# encoder.net
KiCad netlist of a schematic drawn in Altium Designer
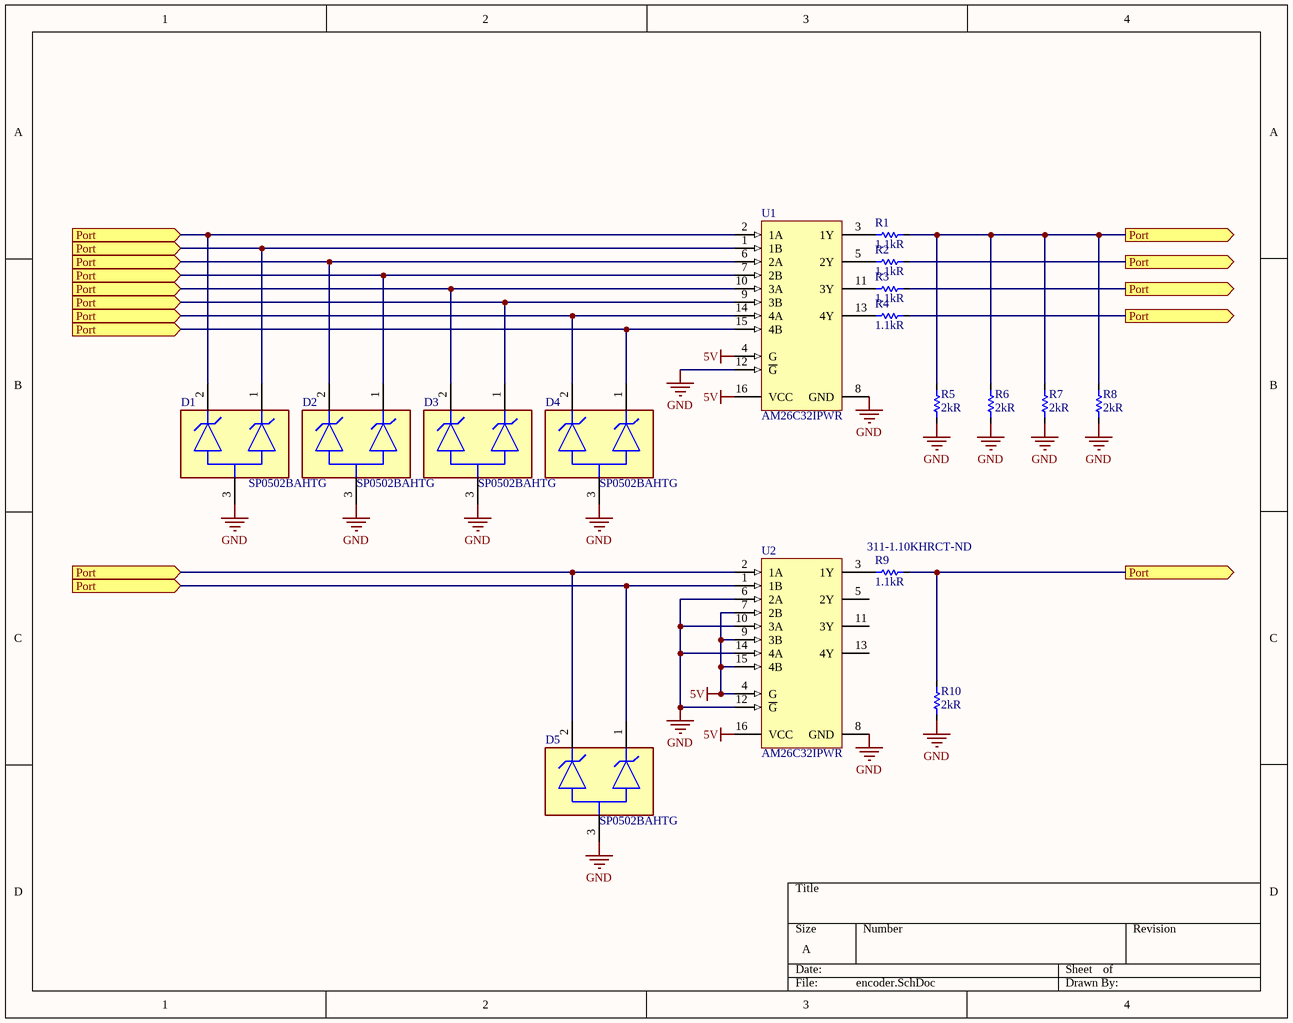
[diagram p0: encoder.SchDoc]

(export (version "E")
  (design (tool "Eeschema 10.0.6"))
  (components
    (comp (ref "D1")
      (value "SP0502BAHTG")
      (footprint "FP-SP0502BAH-MFG")
      (description "8.5V Clamp Ipp Tvs Diode Surface Mount SOT-23-3")
      (fields (field (name "OCTOPART") "https://octopart.com/sp0502bahtg-littelfuse-66370"))
      (libsource (lib "Altium Content Vault") (part "029d71e643ebb86ed7cc400ee026b5c"))
    )
    (comp (ref "D2")
      (value "SP0502BAHTG")
      (footprint "FP-SP0502BAH-MFG")
      (description "8.5V Clamp Ipp Tvs Diode Surface Mount SOT-23-3")
      (fields (field (name "OCTOPART") "https://octopart.com/sp0502bahtg-littelfuse-66370"))
      (libsource (lib "Altium Content Vault") (part "029d71e643ebb86ed7cc400ee026b5c"))
    )
    (comp (ref "D3")
      (value "SP0502BAHTG")
      (footprint "FP-SP0502BAH-MFG")
      (description "8.5V Clamp Ipp Tvs Diode Surface Mount SOT-23-3")
      (fields (field (name "OCTOPART") "https://octopart.com/sp0502bahtg-littelfuse-66370"))
      (libsource (lib "Altium Content Vault") (part "029d71e643ebb86ed7cc400ee026b5c"))
    )
    (comp (ref "D4")
      (value "SP0502BAHTG")
      (footprint "FP-SP0502BAH-MFG")
      (description "8.5V Clamp Ipp Tvs Diode Surface Mount SOT-23-3")
      (fields (field (name "OCTOPART") "https://octopart.com/sp0502bahtg-littelfuse-66370"))
      (libsource (lib "Altium Content Vault") (part "029d71e643ebb86ed7cc400ee026b5c"))
    )
    (comp (ref "D5")
      (value "SP0502BAHTG")
      (footprint "FP-SP0502BAH-MFG")
      (description "8.5V Clamp Ipp Tvs Diode Surface Mount SOT-23-3")
      (fields (field (name "OCTOPART") "https://octopart.com/sp0502bahtg-littelfuse-66370"))
      (libsource (lib "Altium Content Vault") (part "029d71e643ebb86ed7cc400ee026b5c"))
    )
    (comp (ref "R1")
      (value "1.1kR")
      (footprint "RESC1005N")
      (description "RES SMD 1.1K OHM 1% 1/10W 0603")
      (fields
        (field (name "MANUFACTURER") "Yageo")
        (field (name "MANUFACTURER PART NUMBER") "RC0603FR-071K1L")
      )
      (libsource (lib "my parts library") (part "Resistor"))
    )
    (comp (ref "R2")
      (value "1.1kR")
      (footprint "RESC1005N")
      (description "RES SMD 1.1K OHM 1% 1/10W 0603")
      (fields
        (field (name "MANUFACTURER") "Yageo")
        (field (name "MANUFACTURER PART NUMBER") "RC0603FR-071K1L")
      )
      (libsource (lib "my parts library") (part "Resistor"))
    )
    (comp (ref "R3")
      (value "1.1kR")
      (footprint "RESC1005N")
      (description "RES SMD 1.1K OHM 1% 1/10W 0603")
      (fields
        (field (name "MANUFACTURER") "Yageo")
        (field (name "MANUFACTURER PART NUMBER") "RC0603FR-071K1L")
      )
      (libsource (lib "my parts library") (part "Resistor"))
    )
    (comp (ref "R4")
      (value "1.1kR")
      (footprint "RESC1005N")
      (description "RES SMD 1.1K OHM 1% 1/10W 0603")
      (fields
        (field (name "MANUFACTURER") "Yageo")
        (field (name "MANUFACTURER PART NUMBER") "RC0603FR-071K1L")
      )
      (libsource (lib "my parts library") (part "Resistor"))
    )
    (comp (ref "R5")
      (value "2kR")
      (footprint "RESC1005N")
      (description "YAGEO - RC0603FR-072KL - RES, THICK FILM, 2K, 1%, 0.1W, 0603")
      (fields
        (field (name "MANUFACTURER") "Yageo")
        (field (name "MANUFACTURER PART NUMBER") "RC0603FR-072KL")
      )
      (libsource (lib "my parts library") (part "Resistor"))
    )
    (comp (ref "R6")
      (value "2kR")
      (footprint "RESC1005N")
      (description "YAGEO - RC0603FR-072KL - RES, THICK FILM, 2K, 1%, 0.1W, 0603")
      (fields
        (field (name "MANUFACTURER") "Yageo")
        (field (name "MANUFACTURER PART NUMBER") "RC0603FR-072KL")
      )
      (libsource (lib "my parts library") (part "Resistor"))
    )
    (comp (ref "R7")
      (value "2kR")
      (footprint "RESC1005N")
      (description "YAGEO - RC0603FR-072KL - RES, THICK FILM, 2K, 1%, 0.1W, 0603")
      (fields
        (field (name "MANUFACTURER") "Yageo")
        (field (name "MANUFACTURER PART NUMBER") "RC0603FR-072KL")
      )
      (libsource (lib "my parts library") (part "Resistor"))
    )
    (comp (ref "R8")
      (value "2kR")
      (footprint "RESC1005N")
      (description "YAGEO - RC0603FR-072KL - RES, THICK FILM, 2K, 1%, 0.1W, 0603")
      (fields
        (field (name "MANUFACTURER") "Yageo")
        (field (name "MANUFACTURER PART NUMBER") "RC0603FR-072KL")
      )
      (libsource (lib "my parts library") (part "Resistor"))
    )
    (comp (ref "R9")
      (value "1.1kR")
      (footprint "RESC1005N")
      (description "RES SMD 1.1K OHM 1% 1/10W 0603")
      (fields
        (field (name "SUPPLIER PART NUMBER 1") "311-1.10KHRCT-ND")
        (field (name "MANUFACTURER") "Yageo")
        (field (name "MANUFACTURER PART NUMBER") "RC0603FR-071K1L")
      )
      (libsource (lib "my parts library") (part "Resistor"))
    )
    (comp (ref "R10")
      (value "2kR")
      (footprint "RESC1005N")
      (description "YAGEO - RC0603FR-072KL - RES, THICK FILM, 2K, 1%, 0.1W, 0603")
      (fields
        (field (name "MANUFACTURER") "Yageo")
        (field (name "MANUFACTURER PART NUMBER") "RC0603FR-072KL")
      )
      (libsource (lib "my parts library") (part "Resistor"))
    )
    (comp (ref "U1")
      (value "AM26C32IPWR")
      (footprint "PW0016A_L")
      (description "IC RCVR RS422 QUAD DIFF 16TSSOP")
      (fields (field (name "MANUFACTURER") "Texas Instruments"))
      (libsource (lib "Altium Content Vault") (part "TI-AM26C32-TSSOP_PW-16"))
    )
    (comp (ref "U2")
      (value "AM26C32IPWR")
      (footprint "PW0016A_L")
      (description "IC RCVR RS422 QUAD DIFF 16TSSOP")
      (fields (field (name "MANUFACTURER") "Texas Instruments"))
      (libsource (lib "Altium Content Vault") (part "TI-AM26C32-TSSOP_PW-16"))
    )
  )
  (nets
    (net (code "1") (name "/Port") (class "Default")
      (node (ref "D1") (pin "1") (pinfunction "1_CATHODE_1") (pintype "passive"))
      (node (ref "D1") (pin "2") (pinfunction "2_CATHODE_2") (pintype "passive"))
      (node (ref "D2") (pin "1") (pinfunction "1_CATHODE_1") (pintype "passive"))
      (node (ref "D2") (pin "2") (pinfunction "2_CATHODE_2") (pintype "passive"))
      (node (ref "D3") (pin "1") (pinfunction "1_CATHODE_1") (pintype "passive"))
      (node (ref "D3") (pin "2") (pinfunction "2_CATHODE_2") (pintype "passive"))
      (node (ref "D4") (pin "1") (pinfunction "1_CATHODE_1") (pintype "passive"))
      (node (ref "D4") (pin "2") (pinfunction "2_CATHODE_2") (pintype "passive"))
      (node (ref "D5") (pin "1") (pinfunction "1_CATHODE_1") (pintype "passive"))
      (node (ref "D5") (pin "2") (pinfunction "2_CATHODE_2") (pintype "passive"))
      (node (ref "R1") (pin "2") (pinfunction "2_2") (pintype "passive"))
      (node (ref "R10") (pin "1") (pinfunction "1_1") (pintype "passive"))
      (node (ref "R2") (pin "2") (pinfunction "2_2") (pintype "passive"))
      (node (ref "R3") (pin "2") (pinfunction "2_2") (pintype "passive"))
      (node (ref "R4") (pin "2") (pinfunction "2_2") (pintype "passive"))
      (node (ref "R5") (pin "1") (pinfunction "1_1") (pintype "passive"))
      (node (ref "R6") (pin "1") (pinfunction "1_1") (pintype "passive"))
      (node (ref "R7") (pin "1") (pinfunction "1_1") (pintype "passive"))
      (node (ref "R8") (pin "1") (pinfunction "1_1") (pintype "passive"))
      (node (ref "R9") (pin "2") (pinfunction "2_2") (pintype "passive"))
      (node (ref "U1") (pin "1") (pinfunction "1B_1") (pintype "input"))
      (node (ref "U1") (pin "10") (pinfunction "3A_10") (pintype "input"))
      (node (ref "U1") (pin "14") (pinfunction "4A_14") (pintype "input"))
      (node (ref "U1") (pin "15") (pinfunction "4B_15") (pintype "input"))
      (node (ref "U1") (pin "2") (pinfunction "1A_2") (pintype "input"))
      (node (ref "U1") (pin "6") (pinfunction "2A_6") (pintype "input"))
      (node (ref "U1") (pin "7") (pinfunction "2B_7") (pintype "input"))
      (node (ref "U1") (pin "9") (pinfunction "3B_9") (pintype "input"))
      (node (ref "U2") (pin "1") (pinfunction "1B_1") (pintype "input"))
      (node (ref "U2") (pin "2") (pinfunction "1A_2") (pintype "input"))
    )
    (net (code "2") (name "5V") (class "Default")
      (node (ref "U1") (pin "16") (pinfunction "VCC_16") (pintype "power_in"))
      (node (ref "U1") (pin "4") (pinfunction "G_4") (pintype "input"))
      (node (ref "U2") (pin "15") (pinfunction "4B_15") (pintype "input"))
      (node (ref "U2") (pin "16") (pinfunction "VCC_16") (pintype "power_in"))
      (node (ref "U2") (pin "4") (pinfunction "G_4") (pintype "input"))
      (node (ref "U2") (pin "7") (pinfunction "2B_7") (pintype "input"))
      (node (ref "U2") (pin "9") (pinfunction "3B_9") (pintype "input"))
    )
    (net (code "3") (name "GND") (class "Default")
      (node (ref "D1") (pin "3") (pinfunction "COMMON_ANODE_3") (pintype "passive"))
      (node (ref "D2") (pin "3") (pinfunction "COMMON_ANODE_3") (pintype "passive"))
      (node (ref "D3") (pin "3") (pinfunction "COMMON_ANODE_3") (pintype "passive"))
      (node (ref "D4") (pin "3") (pinfunction "COMMON_ANODE_3") (pintype "passive"))
      (node (ref "D5") (pin "3") (pinfunction "COMMON_ANODE_3") (pintype "passive"))
      (node (ref "R10") (pin "2") (pinfunction "2_2") (pintype "passive"))
      (node (ref "R5") (pin "2") (pinfunction "2_2") (pintype "passive"))
      (node (ref "R6") (pin "2") (pinfunction "2_2") (pintype "passive"))
      (node (ref "R7") (pin "2") (pinfunction "2_2") (pintype "passive"))
      (node (ref "R8") (pin "2") (pinfunction "2_2") (pintype "passive"))
      (node (ref "U1") (pin "12") (pinfunction "~{G}_12") (pintype "input"))
      (node (ref "U1") (pin "8") (pinfunction "GND_8") (pintype "power_in"))
      (node (ref "U2") (pin "10") (pinfunction "3A_10") (pintype "input"))
      (node (ref "U2") (pin "12") (pinfunction "~{G}_12") (pintype "input"))
      (node (ref "U2") (pin "14") (pinfunction "4A_14") (pintype "input"))
      (node (ref "U2") (pin "6") (pinfunction "2A_6") (pintype "input"))
      (node (ref "U2") (pin "8") (pinfunction "GND_8") (pintype "power_in"))
    )
    (net (code "4") (name "Net-(U1-1Y)") (class "Default")
      (node (ref "R1") (pin "1") (pinfunction "1_1") (pintype "passive"))
      (node (ref "U1") (pin "3") (pinfunction "1Y_3") (pintype "tri_state"))
    )
    (net (code "5") (name "Net-(U1-2Y)") (class "Default")
      (node (ref "R2") (pin "1") (pinfunction "1_1") (pintype "passive"))
      (node (ref "U1") (pin "5") (pinfunction "2Y_5") (pintype "tri_state"))
    )
    (net (code "6") (name "Net-(U1-3Y)") (class "Default")
      (node (ref "R3") (pin "1") (pinfunction "1_1") (pintype "passive"))
      (node (ref "U1") (pin "11") (pinfunction "3Y_11") (pintype "tri_state"))
    )
    (net (code "7") (name "Net-(U1-4Y)") (class "Default")
      (node (ref "R4") (pin "1") (pinfunction "1_1") (pintype "passive"))
      (node (ref "U1") (pin "13") (pinfunction "4Y_13") (pintype "tri_state"))
    )
    (net (code "8") (name "Net-(U2-1Y)") (class "Default")
      (node (ref "R9") (pin "1") (pinfunction "1_1") (pintype "passive"))
      (node (ref "U2") (pin "3") (pinfunction "1Y_3") (pintype "tri_state"))
    )
    (net (code "9") (name "unconnected-(U2-2Y-Pad5)") (class "Default")
      (node (ref "U2") (pin "5") (pinfunction "2Y_5") (pintype "tri_state"))
    )
    (net (code "10") (name "unconnected-(U2-3Y-Pad11)") (class "Default")
      (node (ref "U2") (pin "11") (pinfunction "3Y_11") (pintype "tri_state"))
    )
    (net (code "11") (name "unconnected-(U2-4Y-Pad13)") (class "Default")
      (node (ref "U2") (pin "13") (pinfunction "4Y_13") (pintype "tri_state"))
    )
  )
)
